# musicbox-interface.net
KiCad netlist of a schematic drawn in EAGLE
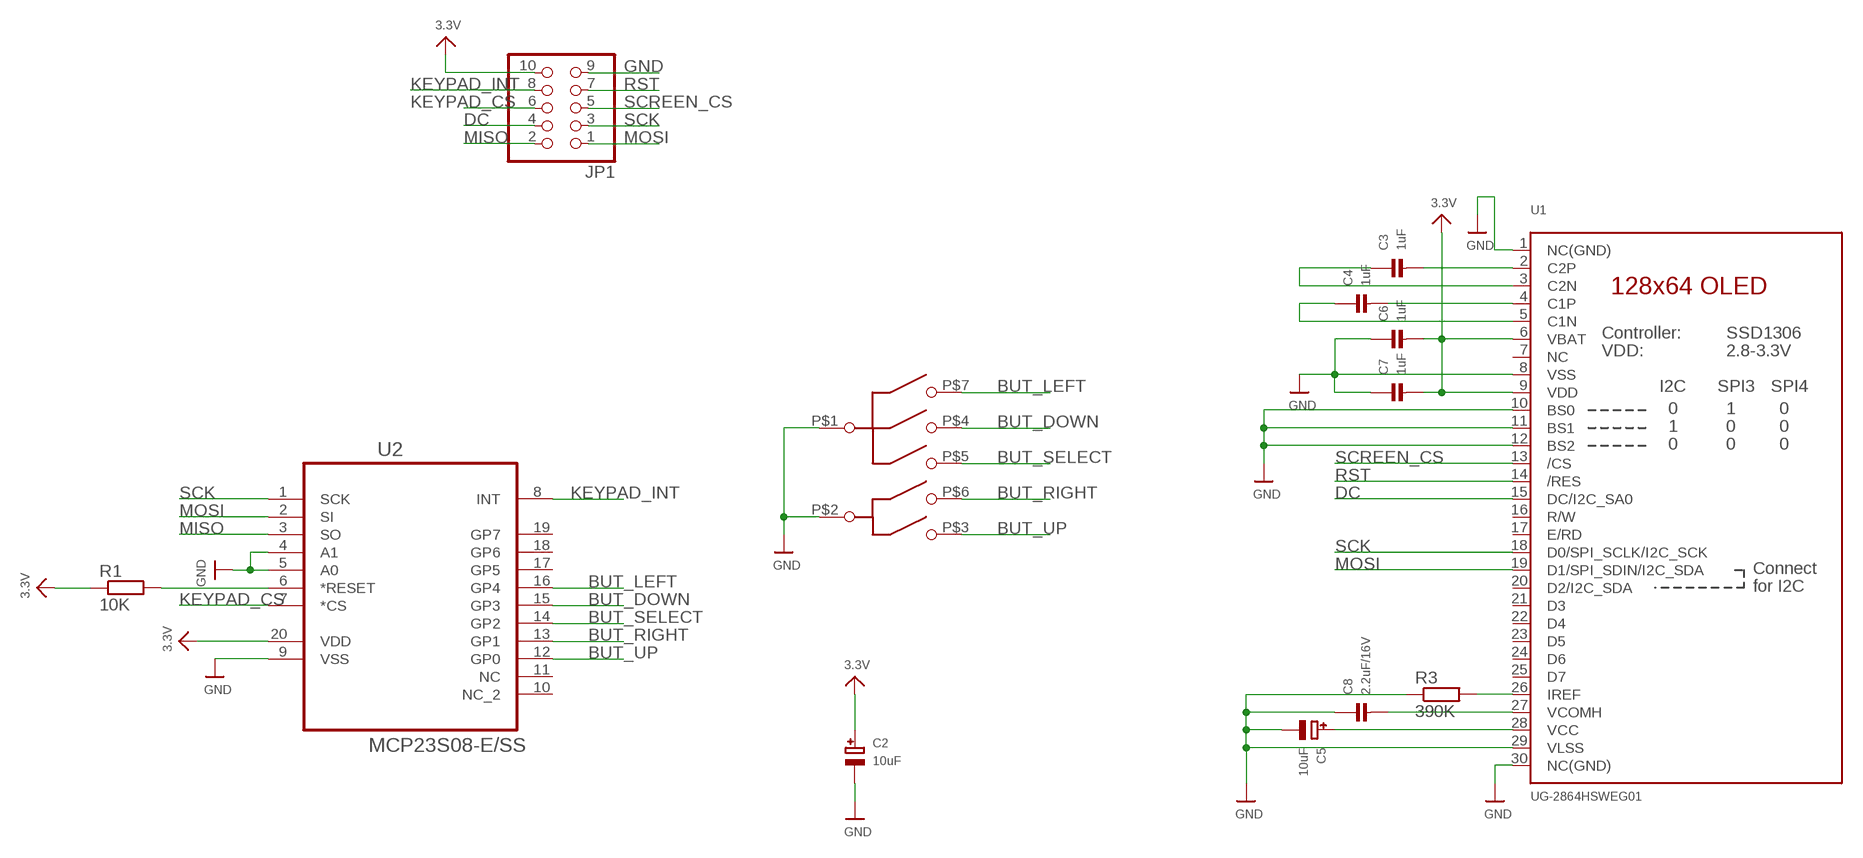
[diagram p0: schematic, sheet 1]

(export (version "E")
  (design (tool "Eeschema 10.0.6"))
  (components
    (comp (ref "C2")
      (value "10uF")
      (footprint "eagle-import:EIA3216-18_A-R")
      (libsource (lib "eagle-import") (part "CAP_TANTALUMA/3216_REFLOW"))
    )
    (comp (ref "C3")
      (value "1uF")
      (footprint "eagle-import:0603")
      (libsource (lib "eagle-import") (part "CAP_CERAMIC0603"))
    )
    (comp (ref "C4")
      (value "1uF")
      (footprint "eagle-import:0603")
      (libsource (lib "eagle-import") (part "CAP_CERAMIC0603"))
    )
    (comp (ref "C5")
      (value "10uF")
      (footprint "eagle-import:EIA3216-18_A-R")
      (libsource (lib "eagle-import") (part "CAP_TANTALUMA/3216_REFLOW"))
    )
    (comp (ref "C6")
      (value "1uF")
      (footprint "eagle-import:0603")
      (libsource (lib "eagle-import") (part "CAP_CERAMIC0603"))
    )
    (comp (ref "C7")
      (value "1uF")
      (footprint "eagle-import:0603")
      (libsource (lib "eagle-import") (part "CAP_CERAMIC0603"))
    )
    (comp (ref "C8")
      (value "2.2uF/16V")
      (footprint "eagle-import:0603")
      (libsource (lib "eagle-import") (part "CAP_CERAMIC0603"))
    )
    (comp (ref "JP1")
      (value "HEADER-2X5")
      (footprint "eagle-import:2X05")
      (libsource (lib "eagle-import") (part "HEADER-2X5"))
    )
    (comp (ref "R1")
      (value "10K")
      (footprint "eagle-import:R0603")
      (libsource (lib "eagle-import") (part "R-EU_R0603"))
    )
    (comp (ref "R3")
      (value "390K")
      (footprint "eagle-import:R0603")
      (libsource (lib "eagle-import") (part "R-EU_R0603"))
    )
    (comp (ref "U$5")
      (value "TPA")
      (footprint "eagle-import:SMT")
      (libsource (lib "eagle-import") (part "TPA"))
    )
    (comp (ref "U1")
      (value "UG-2864HSWEG01")
      (footprint "eagle-import:UG-2864HSWEG01_0.96IN_WRAPAROUND")
      (libsource (lib "eagle-import") (part "DISP_OLED_UG-2864HSWEG010.96{dblquote}"))
    )
    (comp (ref "U2")
      (value "MCP23S08-E/SS")
      (footprint "eagle-import:SOP65P780X200-20N")
      (libsource (lib "eagle-import") (part "MCP23S08-E/SS"))
    )
  )
  (nets
    (net (code "1") (name "/BUT_DOWN") (class "Default")
      (node (ref "U$5") (pin "P$4") (pinfunction "DOWN_P$4") (pintype "bidirectional"))
      (node (ref "U2") (pin "15") (pinfunction "GP3_15") (pintype "bidirectional"))
    )
    (net (code "2") (name "/BUT_LEFT") (class "Default")
      (node (ref "U$5") (pin "P$7") (pinfunction "LEFT_P$7") (pintype "bidirectional"))
      (node (ref "U2") (pin "16") (pinfunction "GP4_16") (pintype "bidirectional"))
    )
    (net (code "3") (name "/BUT_RIGHT") (class "Default")
      (node (ref "U$5") (pin "P$6") (pinfunction "RIGHT_P$6") (pintype "bidirectional"))
      (node (ref "U2") (pin "13") (pinfunction "GP1_13") (pintype "bidirectional"))
    )
    (net (code "4") (name "/BUT_SELECT") (class "Default")
      (node (ref "U$5") (pin "P$5") (pinfunction "SELECT_P$5") (pintype "bidirectional"))
      (node (ref "U2") (pin "14") (pinfunction "GP2_14") (pintype "bidirectional"))
    )
    (net (code "5") (name "/BUT_UP") (class "Default")
      (node (ref "U$5") (pin "P$3") (pinfunction "UP_P$3") (pintype "bidirectional"))
      (node (ref "U2") (pin "12") (pinfunction "GP0_12") (pintype "bidirectional"))
    )
    (net (code "6") (name "/DC") (class "Default")
      (node (ref "JP1") (pin "4") (pinfunction "4_4") (pintype "passive"))
      (node (ref "U1") (pin "15") (pinfunction "DC/I2C_SA0_15") (pintype "input"))
    )
    (net (code "7") (name "/KEYPAD_CS") (class "Default")
      (node (ref "JP1") (pin "6") (pinfunction "6_6") (pintype "passive"))
      (node (ref "U2") (pin "7") (pinfunction "*CS_7") (pintype "input"))
    )
    (net (code "8") (name "/KEYPAD_INT") (class "Default")
      (node (ref "JP1") (pin "8") (pinfunction "8_8") (pintype "passive"))
      (node (ref "U2") (pin "8") (pinfunction "INT_8") (pintype "output"))
    )
    (net (code "9") (name "/MISO") (class "Default")
      (node (ref "JP1") (pin "2") (pinfunction "2_2") (pintype "passive"))
      (node (ref "U2") (pin "3") (pinfunction "SO_3") (pintype "bidirectional"))
    )
    (net (code "10") (name "/MOSI") (class "Default")
      (node (ref "JP1") (pin "1") (pinfunction "1_1") (pintype "passive"))
      (node (ref "U1") (pin "19") (pinfunction "D1/SPI_SDIN/I2C_SDA_19") (pintype "bidirectional"))
      (node (ref "U2") (pin "2") (pinfunction "SI_2") (pintype "bidirectional"))
    )
    (net (code "11") (name "/RST") (class "Default")
      (node (ref "JP1") (pin "7") (pinfunction "7_7") (pintype "passive"))
      (node (ref "U1") (pin "14") (pinfunction "/RES_14") (pintype "input"))
    )
    (net (code "12") (name "/SCK") (class "Default")
      (node (ref "JP1") (pin "3") (pinfunction "3_3") (pintype "passive"))
      (node (ref "U1") (pin "18") (pinfunction "D0/SPI_SCLK/I2C_SCK_18") (pintype "bidirectional"))
      (node (ref "U2") (pin "1") (pinfunction "SCK_1") (pintype "input"))
    )
    (net (code "13") (name "/SCREEN_CS") (class "Default")
      (node (ref "JP1") (pin "5") (pinfunction "5_5") (pintype "passive"))
      (node (ref "U1") (pin "13") (pinfunction "/CS_13") (pintype "input"))
    )
    (net (code "14") (name "3.3V") (class "Default")
      (node (ref "C2") (pin "+") (pinfunction "+_+") (pintype "passive"))
      (node (ref "C6") (pin "2") (pinfunction "P$2_2") (pintype "passive"))
      (node (ref "C7") (pin "2") (pinfunction "P$2_2") (pintype "passive"))
      (node (ref "JP1") (pin "10") (pinfunction "10_10") (pintype "passive"))
      (node (ref "R1") (pin "1") (pinfunction "1_1") (pintype "passive"))
      (node (ref "U1") (pin "6") (pinfunction "VBAT_6") (pintype "input"))
      (node (ref "U1") (pin "9") (pinfunction "VDD_9") (pintype "power_in"))
      (node (ref "U2") (pin "20") (pinfunction "VDD_20") (pintype "power_in"))
    )
    (net (code "15") (name "GND") (class "Default")
      (node (ref "C2") (pin "-") (pinfunction "-_-") (pintype "passive"))
      (node (ref "C5") (pin "-") (pinfunction "-_-") (pintype "passive"))
      (node (ref "C6") (pin "1") (pinfunction "P$1_1") (pintype "passive"))
      (node (ref "C7") (pin "1") (pinfunction "P$1_1") (pintype "passive"))
      (node (ref "C8") (pin "1") (pinfunction "P$1_1") (pintype "passive"))
      (node (ref "JP1") (pin "9") (pinfunction "9_9") (pintype "passive"))
      (node (ref "R3") (pin "1") (pinfunction "1_1") (pintype "passive"))
      (node (ref "U$5") (pin "P$1") (pinfunction "COMMON_1_P$1") (pintype "bidirectional"))
      (node (ref "U$5") (pin "P$2") (pinfunction "COMMON_2_P$2") (pintype "bidirectional"))
      (node (ref "U1") (pin "1") (pinfunction "NC(GND)_1") (pintype "input"))
      (node (ref "U1") (pin "10") (pinfunction "BS0_10") (pintype "input"))
      (node (ref "U1") (pin "11") (pinfunction "BS1_11") (pintype "input"))
      (node (ref "U1") (pin "12") (pinfunction "BS2_12") (pintype "input"))
      (node (ref "U1") (pin "29") (pinfunction "VLSS_29") (pintype "power_in"))
      (node (ref "U1") (pin "30") (pinfunction "NC(GND)_30") (pintype "input"))
      (node (ref "U1") (pin "8") (pinfunction "VSS_8") (pintype "power_in"))
      (node (ref "U2") (pin "4") (pinfunction "A1_4") (pintype "input"))
      (node (ref "U2") (pin "5") (pinfunction "A0_5") (pintype "input"))
      (node (ref "U2") (pin "9") (pinfunction "VSS_9") (pintype "passive"))
    )
    (net (code "16") (name "Net-(C3-P$1)") (class "Default")
      (node (ref "C3") (pin "1") (pinfunction "P$1_1") (pintype "passive"))
      (node (ref "U1") (pin "3") (pinfunction "C2N_3") (pintype "input"))
    )
    (net (code "17") (name "Net-(C3-P$2)") (class "Default")
      (node (ref "C3") (pin "2") (pinfunction "P$2_2") (pintype "passive"))
      (node (ref "U1") (pin "2") (pinfunction "C2P_2") (pintype "input"))
    )
    (net (code "18") (name "Net-(C4-P$1)") (class "Default")
      (node (ref "C4") (pin "1") (pinfunction "P$1_1") (pintype "passive"))
      (node (ref "U1") (pin "5") (pinfunction "C1N_5") (pintype "input"))
    )
    (net (code "19") (name "Net-(C4-P$2)") (class "Default")
      (node (ref "C4") (pin "2") (pinfunction "P$2_2") (pintype "passive"))
      (node (ref "U1") (pin "4") (pinfunction "C1P_4") (pintype "input"))
    )
    (net (code "20") (name "Net-(C8-P$2)") (class "Default")
      (node (ref "C8") (pin "2") (pinfunction "P$2_2") (pintype "passive"))
      (node (ref "U1") (pin "27") (pinfunction "VCOMH_27") (pintype "output"))
    )
    (net (code "21") (name "Net-(U1-IREF)") (class "Default")
      (node (ref "R3") (pin "2") (pinfunction "2_2") (pintype "passive"))
      (node (ref "U1") (pin "26") (pinfunction "IREF_26") (pintype "input"))
    )
    (net (code "22") (name "Net-(U1-VCC)") (class "Default")
      (node (ref "C5") (pin "+") (pinfunction "+_+") (pintype "passive"))
      (node (ref "U1") (pin "28") (pinfunction "VCC_28") (pintype "power_in"))
    )
    (net (code "23") (name "Net-(U2-*RESET)") (class "Default")
      (node (ref "R1") (pin "2") (pinfunction "2_2") (pintype "passive"))
      (node (ref "U2") (pin "6") (pinfunction "*RESET_6") (pintype "input"))
    )
    (net (code "24") (name "unconnected-(U1-D2{slash}I2C_SDA-Pad20)") (class "Default")
      (node (ref "U1") (pin "20") (pinfunction "D2/I2C_SDA_20") (pintype "bidirectional"))
    )
    (net (code "25") (name "unconnected-(U1-D3-Pad21)") (class "Default")
      (node (ref "U1") (pin "21") (pinfunction "D3_21") (pintype "bidirectional"))
    )
    (net (code "26") (name "unconnected-(U1-D4-Pad22)") (class "Default")
      (node (ref "U1") (pin "22") (pinfunction "D4_22") (pintype "bidirectional"))
    )
    (net (code "27") (name "unconnected-(U1-D5-Pad23)") (class "Default")
      (node (ref "U1") (pin "23") (pinfunction "D5_23") (pintype "bidirectional"))
    )
    (net (code "28") (name "unconnected-(U1-D6-Pad24)") (class "Default")
      (node (ref "U1") (pin "24") (pinfunction "D6_24") (pintype "bidirectional"))
    )
    (net (code "29") (name "unconnected-(U1-D7-Pad25)") (class "Default")
      (node (ref "U1") (pin "25") (pinfunction "D7_25") (pintype "bidirectional"))
    )
    (net (code "30") (name "unconnected-(U1-E{slash}RD-Pad17)") (class "Default")
      (node (ref "U1") (pin "17") (pinfunction "E/RD_17") (pintype "input"))
    )
    (net (code "31") (name "unconnected-(U1-NC-Pad7)") (class "Default")
      (node (ref "U1") (pin "7") (pinfunction "NC_7") (pintype "no_connect"))
    )
    (net (code "32") (name "unconnected-(U1-R{slash}W-Pad16)") (class "Default")
      (node (ref "U1") (pin "16") (pinfunction "R/W_16") (pintype "input"))
    )
    (net (code "33") (name "unconnected-(U2-GP5-Pad17)") (class "Default")
      (node (ref "U2") (pin "17") (pinfunction "GP5_17") (pintype "bidirectional"))
    )
    (net (code "34") (name "unconnected-(U2-GP6-Pad18)") (class "Default")
      (node (ref "U2") (pin "18") (pinfunction "GP6_18") (pintype "bidirectional"))
    )
    (net (code "35") (name "unconnected-(U2-GP7-Pad19)") (class "Default")
      (node (ref "U2") (pin "19") (pinfunction "GP7_19") (pintype "bidirectional"))
    )
    (net (code "36") (name "unconnected-(U2-NC-Pad11)") (class "Default")
      (node (ref "U2") (pin "11") (pinfunction "NC_11") (pintype "no_connect"))
    )
    (net (code "37") (name "unconnected-(U2-NC_2-Pad10)") (class "Default")
      (node (ref "U2") (pin "10") (pinfunction "NC_2_10") (pintype "no_connect"))
    )
  )
)
